# as14120_x31_usb.net
KiCad netlist of a schematic drawn in Altium Designer
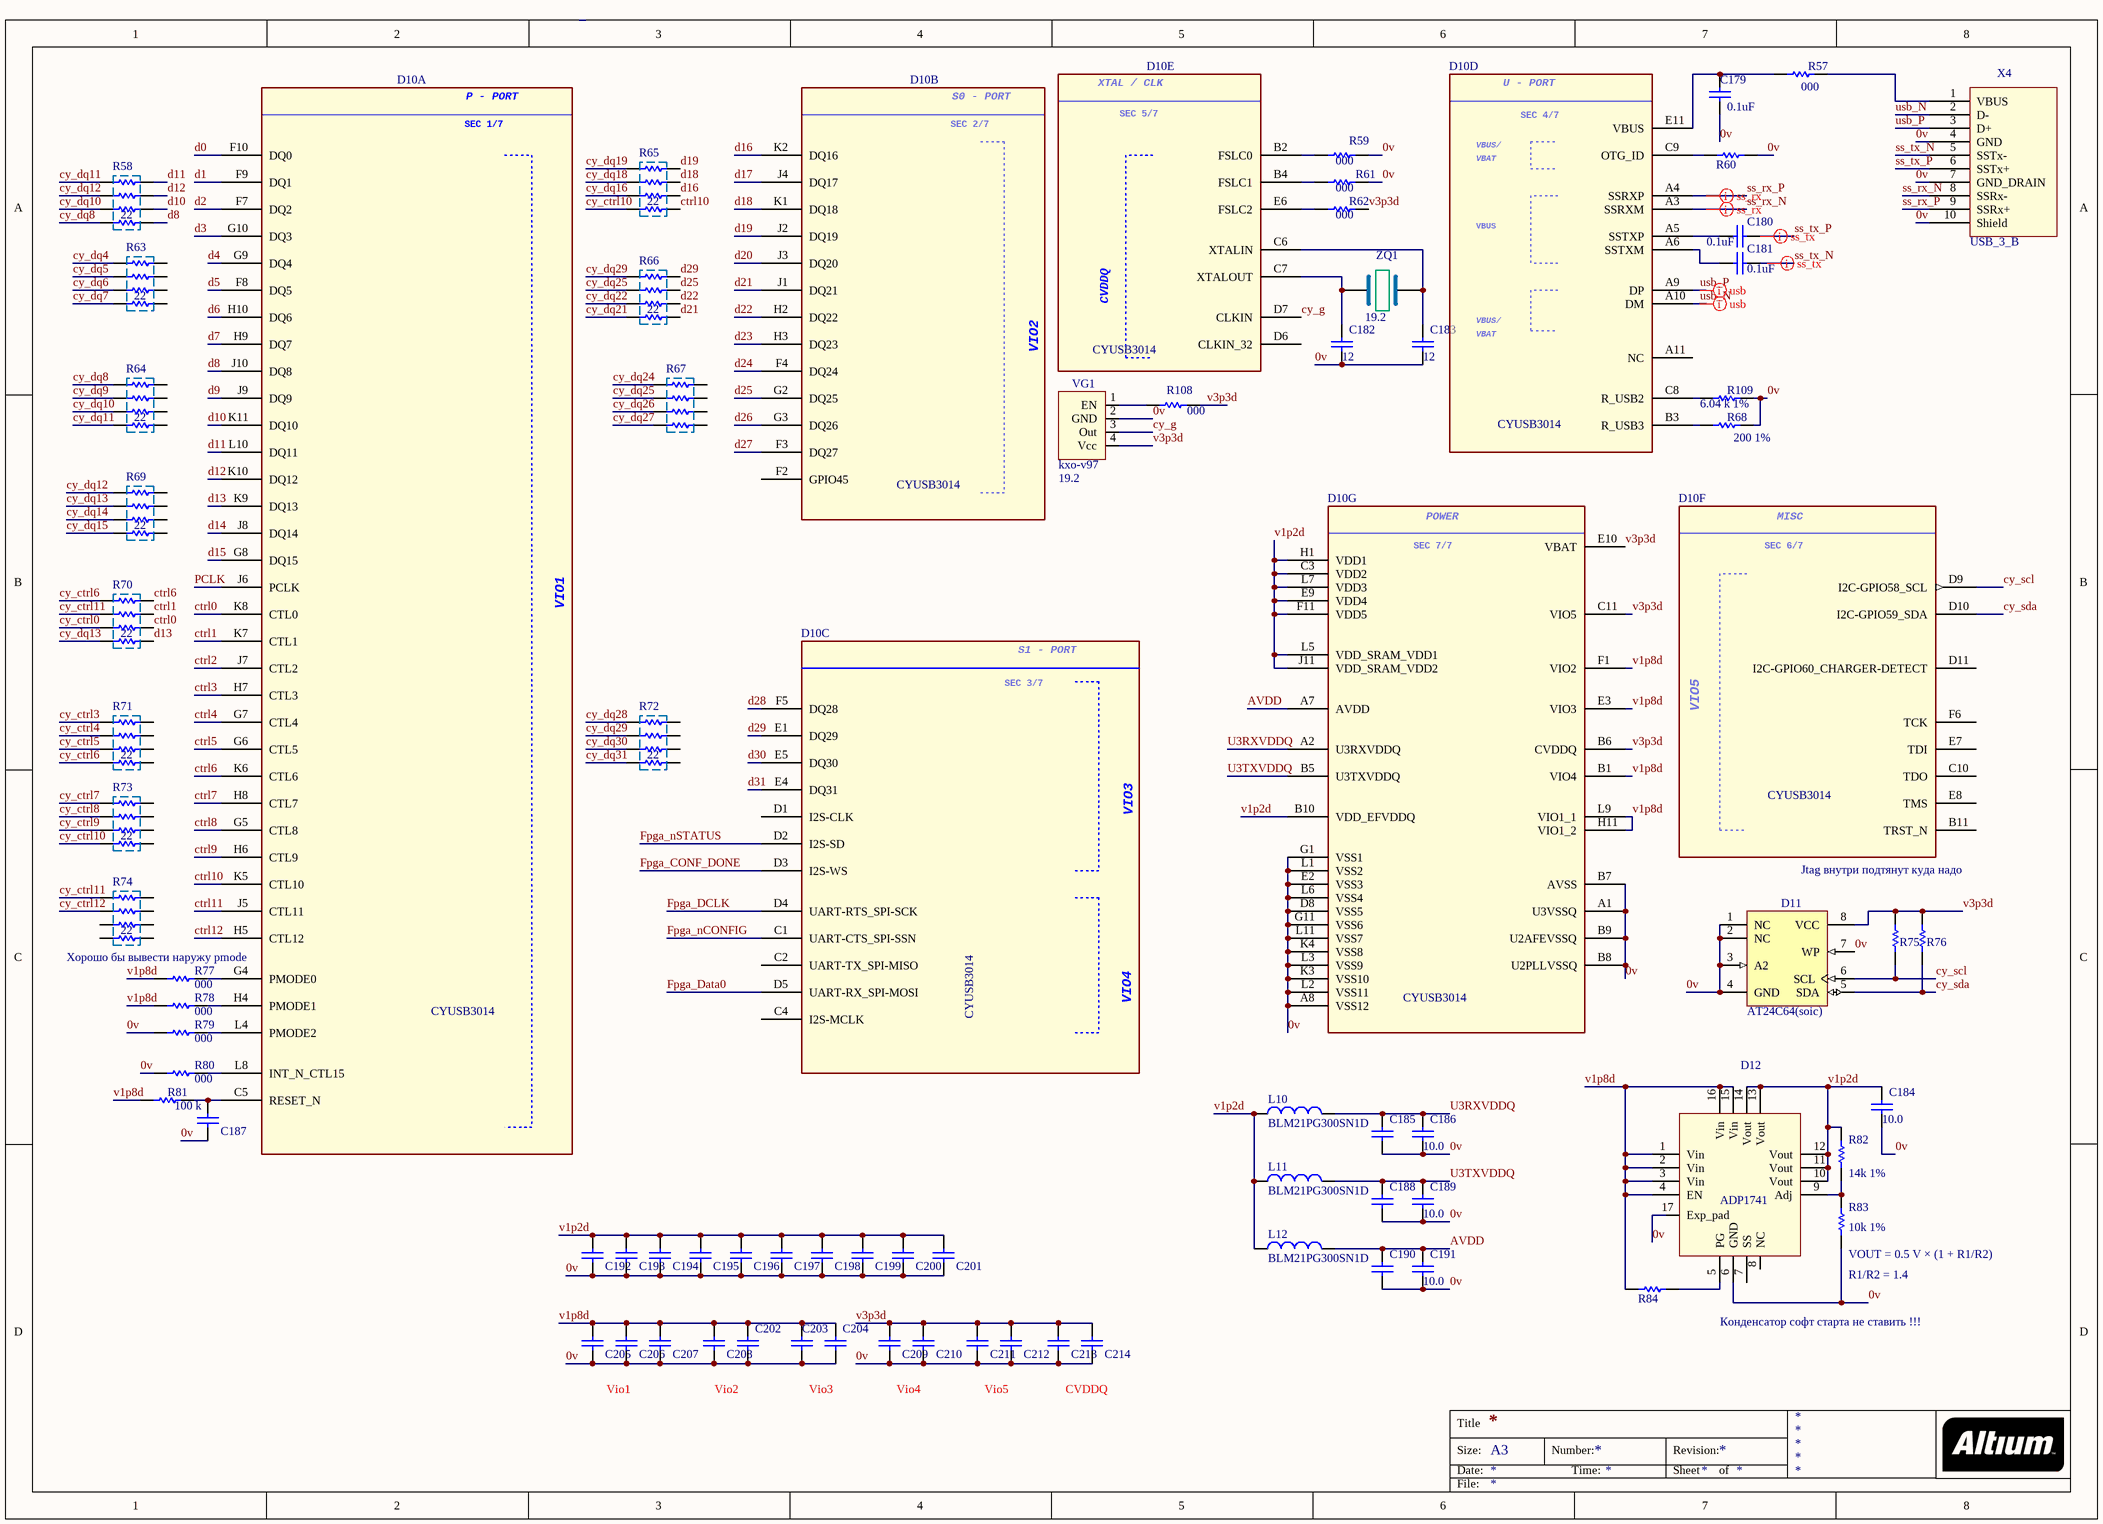
[diagram p0: as14120_x31_usb.SchDoc]

(export (version "E")
  (design (tool "Eeschema 10.0.6"))
  (components
    (comp (ref "C179")
      (value "0.1uF")
      (footprint "CAPC0402(1005)60_M")
      (description "CAP 1uF 10V ±20% 0402 (1005 Metric) Thickness 0.6mm SMD")
      (fields (field (name "TOLERANCE") "±20%") (field (name "Comment") "CAP 1uF 10V 0402(1005)"))
      (libsource (lib "as14120") (part "CAP_0402"))
    )
    (comp (ref "C180")
      (value "0.1uF")
      (footprint "CAPC0402(1005)60_M")
      (description "CAP 1uF 10V ±20% 0402 (1005 Metric) Thickness 0.6mm SMD")
      (fields (field (name "TOLERANCE") "±20%") (field (name "Comment") "CAP 1uF 10V 0402(1005)"))
      (libsource (lib "as14120") (part "CAP_0402"))
    )
    (comp (ref "C181")
      (value "0.1uF")
      (footprint "CAPC0402(1005)60_M")
      (description "CAP 1uF 10V ±20% 0402 (1005 Metric) Thickness 0.6mm SMD")
      (fields (field (name "TOLERANCE") "±20%") (field (name "Comment") "CAP 1uF 10V 0402(1005)"))
      (libsource (lib "as14120") (part "CAP_0402"))
    )
    (comp (ref "C182")
      (value "12")
      (footprint "CAPC0805(2012)100_N")
      (fields (field (name "Comment") "CAP_0805"))
      (libsource (lib "as14120") (part "CAP_0805"))
    )
    (comp (ref "C183")
      (value "12")
      (footprint "CAPC0805(2012)100_N")
      (fields (field (name "Comment") "CAP_0805"))
      (libsource (lib "as14120") (part "CAP_0805"))
    )
    (comp (ref "C184")
      (value "10.0")
      (footprint "CAPC0805(2012)100_N")
      (fields (field (name "Comment") "CAP_0805"))
      (libsource (lib "as14120") (part "CAP_0805"))
    )
    (comp (ref "C185")
      (value "CAP 1uF 10V 0402(1005)")
      (footprint "CAPC0402(1005)60_M")
      (description "CAP 1uF 10V ±20% 0402 (1005 Metric) Thickness 0.6mm SMD")
      (fields (field (name "TOLERANCE") "±20%"))
      (libsource (lib "as14120") (part "CAP_0402"))
    )
    (comp (ref "C186")
      (value "10.0")
      (footprint "CAPC0805(2012)100_N")
      (fields (field (name "Comment") "CAP_0805"))
      (libsource (lib "as14120") (part "CAP_0805"))
    )
    (comp (ref "C187")
      (value "CAP 1uF 10V 0402(1005)")
      (footprint "CAPC0402(1005)60_M")
      (description "CAP 1uF 10V ±20% 0402 (1005 Metric) Thickness 0.6mm SMD")
      (fields (field (name "TOLERANCE") "±20%"))
      (libsource (lib "as14120") (part "CAP_0402"))
    )
    (comp (ref "C188")
      (value "CAP 1uF 10V 0402(1005)")
      (footprint "CAPC0402(1005)60_M")
      (description "CAP 1uF 10V ±20% 0402 (1005 Metric) Thickness 0.6mm SMD")
      (fields (field (name "TOLERANCE") "±20%"))
      (libsource (lib "as14120") (part "CAP_0402"))
    )
    (comp (ref "C189")
      (value "10.0")
      (footprint "CAPC0805(2012)100_N")
      (fields (field (name "Comment") "CAP_0805"))
      (libsource (lib "as14120") (part "CAP_0805"))
    )
    (comp (ref "C190")
      (value "CAP 1uF 10V 0402(1005)")
      (footprint "CAPC0402(1005)60_M")
      (description "CAP 1uF 10V ±20% 0402 (1005 Metric) Thickness 0.6mm SMD")
      (fields (field (name "TOLERANCE") "±20%"))
      (libsource (lib "as14120") (part "CAP_0402"))
    )
    (comp (ref "C191")
      (value "10.0")
      (footprint "CAPC0805(2012)100_N")
      (fields (field (name "Comment") "CAP_0805"))
      (libsource (lib "as14120") (part "CAP_0805"))
    )
    (comp (ref "C192")
      (value "CAP 1uF 10V 0402(1005)")
      (footprint "CAPC0402(1005)60_M")
      (description "CAP 1uF 10V ±20% 0402 (1005 Metric) Thickness 0.6mm SMD")
      (fields (field (name "TOLERANCE") "±20%"))
      (libsource (lib "as14120") (part "CAP_0402"))
    )
    (comp (ref "C193")
      (value "CAP 1uF 10V 0402(1005)")
      (footprint "CAPC0402(1005)60_M")
      (description "CAP 1uF 10V ±20% 0402 (1005 Metric) Thickness 0.6mm SMD")
      (fields (field (name "TOLERANCE") "±20%"))
      (libsource (lib "as14120") (part "CAP_0402"))
    )
    (comp (ref "C194")
      (value "CAP 1uF 10V 0402(1005)")
      (footprint "CAPC0402(1005)60_M")
      (description "CAP 1uF 10V ±20% 0402 (1005 Metric) Thickness 0.6mm SMD")
      (fields (field (name "TOLERANCE") "±20%"))
      (libsource (lib "as14120") (part "CAP_0402"))
    )
    (comp (ref "C195")
      (value "CAP 1uF 10V 0402(1005)")
      (footprint "CAPC0402(1005)60_M")
      (description "CAP 1uF 10V ±20% 0402 (1005 Metric) Thickness 0.6mm SMD")
      (fields (field (name "TOLERANCE") "±20%"))
      (libsource (lib "as14120") (part "CAP_0402"))
    )
    (comp (ref "C196")
      (value "CAP 1uF 10V 0402(1005)")
      (footprint "CAPC0402(1005)60_M")
      (description "CAP 1uF 10V ±20% 0402 (1005 Metric) Thickness 0.6mm SMD")
      (fields (field (name "TOLERANCE") "±20%"))
      (libsource (lib "as14120") (part "CAP_0402"))
    )
    (comp (ref "C197")
      (value "CAP 1uF 10V 0402(1005)")
      (footprint "CAPC0402(1005)60_M")
      (description "CAP 1uF 10V ±20% 0402 (1005 Metric) Thickness 0.6mm SMD")
      (fields (field (name "TOLERANCE") "±20%"))
      (libsource (lib "as14120") (part "CAP_0402"))
    )
    (comp (ref "C198")
      (value "CAP 1uF 10V 0402(1005)")
      (footprint "CAPC0402(1005)60_M")
      (description "CAP 1uF 10V ±20% 0402 (1005 Metric) Thickness 0.6mm SMD")
      (fields (field (name "TOLERANCE") "±20%"))
      (libsource (lib "as14120") (part "CAP_0402"))
    )
    (comp (ref "C199")
      (value "CAP 1uF 10V 0402(1005)")
      (footprint "CAPC0402(1005)60_M")
      (description "CAP 1uF 10V ±20% 0402 (1005 Metric) Thickness 0.6mm SMD")
      (fields (field (name "TOLERANCE") "±20%"))
      (libsource (lib "as14120") (part "CAP_0402"))
    )
    (comp (ref "C200")
      (value "CAP 1uF 10V 0402(1005)")
      (footprint "CAPC0402(1005)60_M")
      (description "CAP 1uF 10V ±20% 0402 (1005 Metric) Thickness 0.6mm SMD")
      (fields (field (name "TOLERANCE") "±20%"))
      (libsource (lib "as14120") (part "CAP_0402"))
    )
    (comp (ref "C201")
      (value "CAP 1uF 10V 0402(1005)")
      (footprint "CAPC0402(1005)60_M")
      (description "CAP 1uF 10V ±20% 0402 (1005 Metric) Thickness 0.6mm SMD")
      (fields (field (name "TOLERANCE") "±20%"))
      (libsource (lib "as14120") (part "CAP_0402"))
    )
    (comp (ref "C202")
      (value "CAP 1uF 10V 0402(1005)")
      (footprint "CAPC0402(1005)60_M")
      (description "CAP 1uF 10V ±20% 0402 (1005 Metric) Thickness 0.6mm SMD")
      (fields (field (name "TOLERANCE") "±20%"))
      (libsource (lib "as14120") (part "CAP_0402"))
    )
    (comp (ref "C203")
      (value "CAP 1uF 10V 0402(1005)")
      (footprint "CAPC0402(1005)60_M")
      (description "CAP 1uF 10V ±20% 0402 (1005 Metric) Thickness 0.6mm SMD")
      (fields (field (name "TOLERANCE") "±20%"))
      (libsource (lib "as14120") (part "CAP_0402"))
    )
    (comp (ref "C204")
      (value "CAP 1uF 10V 0402(1005)")
      (footprint "CAPC0402(1005)60_M")
      (description "CAP 1uF 10V ±20% 0402 (1005 Metric) Thickness 0.6mm SMD")
      (fields (field (name "TOLERANCE") "±20%"))
      (libsource (lib "as14120") (part "CAP_0402"))
    )
    (comp (ref "C205")
      (value "CAP 1uF 10V 0402(1005)")
      (footprint "CAPC0402(1005)60_M")
      (description "CAP 1uF 10V ±20% 0402 (1005 Metric) Thickness 0.6mm SMD")
      (fields (field (name "TOLERANCE") "±20%"))
      (libsource (lib "as14120") (part "CAP_0402"))
    )
    (comp (ref "C206")
      (value "CAP 1uF 10V 0402(1005)")
      (footprint "CAPC0402(1005)60_M")
      (description "CAP 1uF 10V ±20% 0402 (1005 Metric) Thickness 0.6mm SMD")
      (fields (field (name "TOLERANCE") "±20%"))
      (libsource (lib "as14120") (part "CAP_0402"))
    )
    (comp (ref "C207")
      (value "CAP 1uF 10V 0402(1005)")
      (footprint "CAPC0402(1005)60_M")
      (description "CAP 1uF 10V ±20% 0402 (1005 Metric) Thickness 0.6mm SMD")
      (fields (field (name "TOLERANCE") "±20%"))
      (libsource (lib "as14120") (part "CAP_0402"))
    )
    (comp (ref "C208")
      (value "CAP 1uF 10V 0402(1005)")
      (footprint "CAPC0402(1005)60_M")
      (description "CAP 1uF 10V ±20% 0402 (1005 Metric) Thickness 0.6mm SMD")
      (fields (field (name "TOLERANCE") "±20%"))
      (libsource (lib "as14120") (part "CAP_0402"))
    )
    (comp (ref "C209")
      (value "CAP 1uF 10V 0402(1005)")
      (footprint "CAPC0402(1005)60_M")
      (description "CAP 1uF 10V ±20% 0402 (1005 Metric) Thickness 0.6mm SMD")
      (fields (field (name "TOLERANCE") "±20%"))
      (libsource (lib "as14120") (part "CAP_0402"))
    )
    (comp (ref "C210")
      (value "CAP 1uF 10V 0402(1005)")
      (footprint "CAPC0402(1005)60_M")
      (description "CAP 1uF 10V ±20% 0402 (1005 Metric) Thickness 0.6mm SMD")
      (fields (field (name "TOLERANCE") "±20%"))
      (libsource (lib "as14120") (part "CAP_0402"))
    )
    (comp (ref "C211")
      (value "CAP 1uF 10V 0402(1005)")
      (footprint "CAPC0402(1005)60_M")
      (description "CAP 1uF 10V ±20% 0402 (1005 Metric) Thickness 0.6mm SMD")
      (fields (field (name "TOLERANCE") "±20%"))
      (libsource (lib "as14120") (part "CAP_0402"))
    )
    (comp (ref "C212")
      (value "CAP 1uF 10V 0402(1005)")
      (footprint "CAPC0402(1005)60_M")
      (description "CAP 1uF 10V ±20% 0402 (1005 Metric) Thickness 0.6mm SMD")
      (fields (field (name "TOLERANCE") "±20%"))
      (libsource (lib "as14120") (part "CAP_0402"))
    )
    (comp (ref "C213")
      (value "CAP 1uF 10V 0402(1005)")
      (footprint "CAPC0402(1005)60_M")
      (description "CAP 1uF 10V ±20% 0402 (1005 Metric) Thickness 0.6mm SMD")
      (fields (field (name "TOLERANCE") "±20%"))
      (libsource (lib "as14120") (part "CAP_0402"))
    )
    (comp (ref "C214")
      (value "CAP 1uF 10V 0402(1005)")
      (footprint "CAPC0402(1005)60_M")
      (description "CAP 1uF 10V ±20% 0402 (1005 Metric) Thickness 0.6mm SMD")
      (fields (field (name "TOLERANCE") "±20%"))
      (libsource (lib "as14120") (part "CAP_0402"))
    )
    (comp (ref "D10")
      (value "CYUSB3014")
      (footprint "BGA121C80P11X11")
      (libsource (lib "as14120") (part "CYUSB3014-BZXC"))
    )
    (comp (ref "D11")
      (value "AT24C64(soic)")
      (footprint "8S1_N")
      (libsource (lib "Atmel Serial EEPROM") (part "AT24C08BN-SP25-T"))
    )
    (comp (ref "D12") (value "ADP1741") (footprint "CP-16-4_N") (libsource (lib "as14120") (part "ADP1741")))
    (comp (ref "L10")
      (value "BLM21PG300SN1D")
      (footprint "CAPC0805(2012)100_N")
      (libsource (lib "as14120") (part "Ferrite_beat"))
    )
    (comp (ref "L11")
      (value "BLM21PG300SN1D")
      (footprint "CAPC0805(2012)100_N")
      (libsource (lib "as14120") (part "Ferrite_beat"))
    )
    (comp (ref "L12")
      (value "BLM21PG300SN1D")
      (footprint "CAPC0805(2012)100_N")
      (libsource (lib "as14120") (part "Ferrite_beat"))
    )
    (comp (ref "R57")
      (value "000")
      (footprint "RESC0805(2012)_L")
      (description "1K 0.125W 1% 0805 (2012 Metric)  SMD")
      (fields (field (name "TOLERANCE") "1 %") (field (name "POWER") "0.125 W"))
      (libsource (lib "as14120") (part "RES_0805"))
    )
    (comp (ref "R58") (value "22") (footprint "CAY16") (libsource (lib "as14120") (part "cay16-J4")))
    (comp (ref "R59")
      (value "000")
      (footprint "RESC0603(1608)_L")
      (description "1K 0.1W 5% 0603 (1608 Metric)  SMD")
      (fields (field (name "TOLERANCE") "5 %") (field (name "POWER") "0.1 W"))
      (libsource (lib "as14120") (part "RES_0603"))
    )
    (comp (ref "R60")
      (value "???")
      (footprint "RESC0603(1608)_L")
      (description "1K 0.1W 5% 0603 (1608 Metric)  SMD")
      (fields (field (name "TOLERANCE") "5 %") (field (name "POWER") "0.1 W"))
      (libsource (lib "as14120") (part "RES_0603"))
    )
    (comp (ref "R61")
      (value "000")
      (footprint "RESC0603(1608)_L")
      (description "1K 0.1W 5% 0603 (1608 Metric)  SMD")
      (fields (field (name "TOLERANCE") "5 %") (field (name "POWER") "0.1 W"))
      (libsource (lib "as14120") (part "RES_0603"))
    )
    (comp (ref "R62")
      (value "000")
      (footprint "RESC0603(1608)_L")
      (description "1K 0.1W 5% 0603 (1608 Metric)  SMD")
      (fields (field (name "TOLERANCE") "5 %") (field (name "POWER") "0.1 W"))
      (libsource (lib "as14120") (part "RES_0603"))
    )
    (comp (ref "R63") (value "22") (footprint "CAY16") (libsource (lib "as14120") (part "cay16-J4")))
    (comp (ref "R64") (value "22") (footprint "CAY16") (libsource (lib "as14120") (part "cay16-J4")))
    (comp (ref "R65") (value "22") (footprint "CAY16") (libsource (lib "as14120") (part "cay16-J4")))
    (comp (ref "R66") (value "22") (footprint "CAY16") (libsource (lib "as14120") (part "cay16-J4")))
    (comp (ref "R67") (value "~") (footprint "CAY16") (libsource (lib "as14120") (part "cay16-J4")))
    (comp (ref "R68")
      (value "200 1%")
      (footprint "RESC0805(2012)_L")
      (description "1K 0.125W 1% 0805 (2012 Metric)  SMD")
      (fields (field (name "TOLERANCE") "1 %") (field (name "POWER") "0.125 W"))
      (libsource (lib "as14120") (part "RES_0805"))
    )
    (comp (ref "R69") (value "22") (footprint "CAY16") (libsource (lib "as14120") (part "cay16-J4")))
    (comp (ref "R70") (value "22") (footprint "CAY16") (libsource (lib "as14120") (part "cay16-J4")))
    (comp (ref "R71") (value "22") (footprint "CAY16") (libsource (lib "as14120") (part "cay16-J4")))
    (comp (ref "R72") (value "22") (footprint "CAY16") (libsource (lib "as14120") (part "cay16-J4")))
    (comp (ref "R73") (value "22") (footprint "CAY16") (libsource (lib "as14120") (part "cay16-J4")))
    (comp (ref "R74") (value "22") (footprint "CAY16") (libsource (lib "as14120") (part "cay16-J4")))
    (comp (ref "R75")
      (value "1K 5% 0603(1608)")
      (footprint "RESC0603(1608)_L")
      (description "1K 0.1W 5% 0603 (1608 Metric)  SMD")
      (fields (field (name "TOLERANCE") "5 %") (field (name "POWER") "0.1 W"))
      (libsource (lib "as14120") (part "RES_0603"))
    )
    (comp (ref "R76")
      (value "1K 5% 0603(1608)")
      (footprint "RESC0603(1608)_L")
      (description "1K 0.1W 5% 0603 (1608 Metric)  SMD")
      (fields (field (name "TOLERANCE") "5 %") (field (name "POWER") "0.1 W"))
      (libsource (lib "as14120") (part "RES_0603"))
    )
    (comp (ref "R77")
      (value "000")
      (footprint "RESC0603(1608)_L")
      (description "1K 0.1W 5% 0603 (1608 Metric)  SMD")
      (fields (field (name "TOLERANCE") "5 %") (field (name "POWER") "0.1 W"))
      (libsource (lib "as14120") (part "RES_0603"))
    )
    (comp (ref "R78")
      (value "000")
      (footprint "RESC0603(1608)_L")
      (description "1K 0.1W 5% 0603 (1608 Metric)  SMD")
      (fields (field (name "TOLERANCE") "5 %") (field (name "POWER") "0.1 W"))
      (libsource (lib "as14120") (part "RES_0603"))
    )
    (comp (ref "R79")
      (value "000")
      (footprint "RESC0603(1608)_L")
      (description "1K 0.1W 5% 0603 (1608 Metric)  SMD")
      (fields (field (name "TOLERANCE") "5 %") (field (name "POWER") "0.1 W"))
      (libsource (lib "as14120") (part "RES_0603"))
    )
    (comp (ref "R80")
      (value "000")
      (footprint "RESC0603(1608)_L")
      (description "1K 0.1W 5% 0603 (1608 Metric)  SMD")
      (fields (field (name "TOLERANCE") "5 %") (field (name "POWER") "0.1 W"))
      (libsource (lib "as14120") (part "RES_0603"))
    )
    (comp (ref "R81")
      (value "100 k")
      (footprint "RESC0603(1608)_L")
      (description "1K 0.1W 5% 0603 (1608 Metric)  SMD")
      (fields (field (name "TOLERANCE") "5 %") (field (name "POWER") "0.1 W"))
      (libsource (lib "as14120") (part "RES_0603"))
    )
    (comp (ref "R82")
      (value "14k 1%")
      (footprint "RESC0805(2012)_L")
      (description "1K 0.125W 1% 0805 (2012 Metric)  SMD")
      (fields (field (name "TOLERANCE") "1 %") (field (name "POWER") "0.125 W"))
      (libsource (lib "as14120") (part "RES_0805"))
    )
    (comp (ref "R83")
      (value "10k 1%")
      (footprint "RESC0805(2012)_L")
      (description "1K 0.125W 1% 0805 (2012 Metric)  SMD")
      (fields (field (name "TOLERANCE") "1 %") (field (name "POWER") "0.125 W"))
      (libsource (lib "as14120") (part "RES_0805"))
    )
    (comp (ref "R84")
      (value "1K 5% 0603(1608)")
      (footprint "RESC0603(1608)_L")
      (description "1K 0.1W 5% 0603 (1608 Metric)  SMD")
      (fields (field (name "TOLERANCE") "5 %") (field (name "POWER") "0.1 W"))
      (libsource (lib "as14120") (part "RES_0603"))
    )
    (comp (ref "R108")
      (value "000")
      (footprint "RESC0603(1608)_L")
      (description "1K 0.1W 5% 0603 (1608 Metric)  SMD")
      (fields (field (name "TOLERANCE") "5 %") (field (name "POWER") "0.1 W"))
      (libsource (lib "as14120") (part "RES_0603"))
    )
    (comp (ref "R109")
      (value "6.04 k 1%")
      (footprint "RESC0805(2012)_L")
      (description "1K 0.125W 1% 0805 (2012 Metric)  SMD")
      (fields (field (name "TOLERANCE") "1 %") (field (name "POWER") "0.125 W"))
      (libsource (lib "as14120") (part "RES_0805"))
    )
    (comp (ref "VG1")
      (value "kxo-v97")
      (footprint "kxo-v97")
      (fields (field (name "ALTIUM_VALUE") "19.2"))
      (libsource (lib "as14120") (part "kxo-v97"))
    )
    (comp (ref "X4") (value "USB_3_B") (footprint "USB3_B") (libsource (lib "as14120") (part "USB_3_B")))
    (comp (ref "ZQ1")
      (value "19.2")
      (footprint "BCY-W2/E4.7")
      (fields (field (name "Comment") "Resonator"))
      (libsource (lib "as14120") (part "Resonator"))
    )
  )
  (nets
    (net (code "1") (name "/0v") (class "Default")
      (node (ref "C179") (pin "2") (pinfunction "2_2") (pintype "passive"))
      (node (ref "C182") (pin "1") (pinfunction "1_1") (pintype "passive"))
      (node (ref "C183") (pin "1") (pinfunction "1_1") (pintype "passive"))
      (node (ref "C184") (pin "1") (pinfunction "1_1") (pintype "passive"))
      (node (ref "C185") (pin "1") (pinfunction "1_1") (pintype "passive"))
      (node (ref "C186") (pin "1") (pinfunction "1_1") (pintype "passive"))
      (node (ref "C187") (pin "1") (pinfunction "1_1") (pintype "passive"))
      (node (ref "C188") (pin "1") (pinfunction "1_1") (pintype "passive"))
      (node (ref "C189") (pin "1") (pinfunction "1_1") (pintype "passive"))
      (node (ref "C190") (pin "1") (pinfunction "1_1") (pintype "passive"))
      (node (ref "C191") (pin "1") (pinfunction "1_1") (pintype "passive"))
      (node (ref "C192") (pin "1") (pinfunction "1_1") (pintype "passive"))
      (node (ref "C193") (pin "1") (pinfunction "1_1") (pintype "passive"))
      (node (ref "C194") (pin "1") (pinfunction "1_1") (pintype "passive"))
      (node (ref "C195") (pin "1") (pinfunction "1_1") (pintype "passive"))
      (node (ref "C196") (pin "1") (pinfunction "1_1") (pintype "passive"))
      (node (ref "C197") (pin "1") (pinfunction "1_1") (pintype "passive"))
      (node (ref "C198") (pin "1") (pinfunction "1_1") (pintype "passive"))
      (node (ref "C199") (pin "1") (pinfunction "1_1") (pintype "passive"))
      (node (ref "C200") (pin "1") (pinfunction "1_1") (pintype "passive"))
      (node (ref "C201") (pin "1") (pinfunction "1_1") (pintype "passive"))
      (node (ref "C202") (pin "1") (pinfunction "1_1") (pintype "passive"))
      (node (ref "C203") (pin "1") (pinfunction "1_1") (pintype "passive"))
      (node (ref "C204") (pin "1") (pinfunction "1_1") (pintype "passive"))
      (node (ref "C205") (pin "1") (pinfunction "1_1") (pintype "passive"))
      (node (ref "C206") (pin "1") (pinfunction "1_1") (pintype "passive"))
      (node (ref "C207") (pin "1") (pinfunction "1_1") (pintype "passive"))
      (node (ref "C208") (pin "1") (pinfunction "1_1") (pintype "passive"))
      (node (ref "C209") (pin "1") (pinfunction "1_1") (pintype "passive"))
      (node (ref "C210") (pin "1") (pinfunction "1_1") (pintype "passive"))
      (node (ref "C211") (pin "1") (pinfunction "1_1") (pintype "passive"))
      (node (ref "C212") (pin "1") (pinfunction "1_1") (pintype "passive"))
      (node (ref "C213") (pin "1") (pinfunction "1_1") (pintype "passive"))
      (node (ref "C214") (pin "1") (pinfunction "1_1") (pintype "passive"))
      (node (ref "D10") (pin "A1") (pinfunction "U3VSSQ_A1") (pintype "passive"))
      (node (ref "D10") (pin "A8") (pinfunction "VSS12_A8") (pintype "passive"))
      (node (ref "D10") (pin "B7") (pinfunction "AVSS_B7") (pintype "passive"))
      (node (ref "D10") (pin "B8") (pinfunction "U2PLLVSSQ_B8") (pintype "passive"))
      (node (ref "D10") (pin "B9") (pinfunction "U2AFEVSSQ_B9") (pintype "passive"))
      (node (ref "D10") (pin "D8") (pinfunction "VSS5_D8") (pintype "passive"))
      (node (ref "D10") (pin "E2") (pinfunction "VSS3_E2") (pintype "passive"))
      (node (ref "D10") (pin "G1") (pinfunction "VSS1_G1") (pintype "passive"))
      (node (ref "D10") (pin "G11") (pinfunction "VSS6_G11") (pintype "passive"))
      (node (ref "D10") (pin "K3") (pinfunction "VSS10_K3") (pintype "passive"))
      (node (ref "D10") (pin "K4") (pinfunction "VSS8_K4") (pintype "passive"))
      (node (ref "D10") (pin "L1") (pinfunction "VSS2_L1") (pintype "passive"))
      (node (ref "D10") (pin "L11") (pinfunction "VSS7_L11") (pintype "passive"))
      (node (ref "D10") (pin "L2") (pinfunction "VSS11_L2") (pintype "passive"))
      (node (ref "D10") (pin "L3") (pinfunction "VSS9_L3") (pintype "passive"))
      (node (ref "D10") (pin "L6") (pinfunction "VSS4_L6") (pintype "passive"))
      (node (ref "D11") (pin "1") (pinfunction "NC_1") (pintype "passive"))
      (node (ref "D11") (pin "2") (pinfunction "NC_2") (pintype "passive"))
      (node (ref "D11") (pin "3") (pinfunction "A2_3") (pintype "input"))
      (node (ref "D11") (pin "4") (pinfunction "GND_4") (pintype "power_in"))
      (node (ref "D11") (pin "7") (pinfunction "WP_7") (pintype "input"))
      (node (ref "D12") (pin "17") (pinfunction "Exp_pad_17") (pintype "passive"))
      (node (ref "D12") (pin "6") (pinfunction "GND_6") (pintype "passive"))
      (node (ref "R109") (pin "2") (pinfunction "2_2") (pintype "passive"))
      (node (ref "R59") (pin "1") (pinfunction "1_1") (pintype "passive"))
      (node (ref "R60") (pin "2") (pinfunction "2_2") (pintype "passive"))
      (node (ref "R61") (pin "1") (pinfunction "1_1") (pintype "passive"))
      (node (ref "R68") (pin "2") (pinfunction "2_2") (pintype "passive"))
      (node (ref "R79") (pin "2") (pinfunction "2_2") (pintype "passive"))
      (node (ref "R80") (pin "2") (pinfunction "2_2") (pintype "passive"))
      (node (ref "R83") (pin "1") (pinfunction "1_1") (pintype "passive"))
      (node (ref "VG1") (pin "2") (pinfunction "GND_2") (pintype "passive"))
      (node (ref "X4") (pin "10") (pinfunction "Shield_10") (pintype "passive"))
      (node (ref "X4") (pin "4") (pinfunction "GND_4") (pintype "passive"))
      (node (ref "X4") (pin "7") (pinfunction "GND_DRAIN_7") (pintype "passive"))
    )
    (net (code "2") (name "/AVDD") (class "Default")
      (node (ref "C190") (pin "2") (pinfunction "2_2") (pintype "passive"))
      (node (ref "C191") (pin "2") (pinfunction "2_2") (pintype "passive"))
      (node (ref "D10") (pin "A7") (pinfunction "AVDD_A7") (pintype "passive"))
      (node (ref "L12") (pin "2") (pinfunction "2_2") (pintype "passive"))
    )
    (net (code "3") (name "/Fpga_CONF_DONE") (class "Default")
      (node (ref "D10") (pin "D3") (pinfunction "I2S-WS_D3") (pintype "passive"))
    )
    (net (code "4") (name "/Fpga_DCLK") (class "Default")
      (node (ref "D10") (pin "D4") (pinfunction "UART-RTS_SPI-SCK_D4") (pintype "passive"))
    )
    (net (code "5") (name "/Fpga_Data0") (class "Default")
      (node (ref "D10") (pin "D5") (pinfunction "UART-RX_SPI-MOSI_D5") (pintype "passive"))
    )
    (net (code "6") (name "/Fpga_nCONFIG") (class "Default")
      (node (ref "D10") (pin "C1") (pinfunction "UART-CTS_SPI-SSN_C1") (pintype "passive"))
    )
    (net (code "7") (name "/Fpga_nSTATUS") (class "Default")
      (node (ref "D10") (pin "D2") (pinfunction "I2S-SD_D2") (pintype "passive"))
    )
    (net (code "8") (name "/PCLK") (class "Default")
      (node (ref "D10") (pin "J6") (pinfunction "PCLK_J6") (pintype "passive"))
    )
    (net (code "9") (name "/U3RXVDDQ") (class "Default")
      (node (ref "C185") (pin "2") (pinfunction "2_2") (pintype "passive"))
      (node (ref "C186") (pin "2") (pinfunction "2_2") (pintype "passive"))
      (node (ref "D10") (pin "A2") (pinfunction "U3RXVDDQ_A2") (pintype "passive"))
      (node (ref "L10") (pin "2") (pinfunction "2_2") (pintype "passive"))
    )
    (net (code "10") (name "/U3TXVDDQ") (class "Default")
      (node (ref "C188") (pin "2") (pinfunction "2_2") (pintype "passive"))
      (node (ref "C189") (pin "2") (pinfunction "2_2") (pintype "passive"))
      (node (ref "D10") (pin "B5") (pinfunction "U3TXVDDQ_B5") (pintype "passive"))
      (node (ref "L11") (pin "2") (pinfunction "2_2") (pintype "passive"))
    )
    (net (code "11") (name "/ctrl0") (class "Default")
      (node (ref "D10") (pin "K8") (pinfunction "CTL0_K8") (pintype "passive"))
      (node (ref "R70") (pin "6") (pinfunction "6_6") (pintype "passive"))
    )
    (net (code "12") (name "/ctrl1") (class "Default")
      (node (ref "D10") (pin "K7") (pinfunction "CTL1_K7") (pintype "passive"))
      (node (ref "R70") (pin "7") (pinfunction "7_7") (pintype "passive"))
    )
    (net (code "13") (name "/ctrl2") (class "Default")
      (node (ref "D10") (pin "J7") (pinfunction "CTL2_J7") (pintype "passive"))
    )
    (net (code "14") (name "/ctrl3") (class "Default")
      (node (ref "D10") (pin "H7") (pinfunction "CTL3_H7") (pintype "passive"))
    )
    (net (code "15") (name "/ctrl4") (class "Default")
      (node (ref "D10") (pin "G7") (pinfunction "CTL4_G7") (pintype "passive"))
    )
    (net (code "16") (name "/ctrl5") (class "Default")
      (node (ref "D10") (pin "G6") (pinfunction "CTL5_G6") (pintype "passive"))
    )
    (net (code "17") (name "/ctrl6") (class "Default")
      (node (ref "D10") (pin "K6") (pinfunction "CTL6_K6") (pintype "passive"))
      (node (ref "R70") (pin "8") (pinfunction "8_8") (pintype "passive"))
    )
    (net (code "18") (name "/ctrl7") (class "Default")
      (node (ref "D10") (pin "H8") (pinfunction "CTL7_H8") (pintype "passive"))
    )
    (net (code "19") (name "/ctrl8") (class "Default")
      (node (ref "D10") (pin "G5") (pinfunction "CTL8_G5") (pintype "passive"))
    )
    (net (code "20") (name "/ctrl9") (class "Default")
      (node (ref "D10") (pin "H6") (pinfunction "CTL9_H6") (pintype "passive"))
    )
    (net (code "21") (name "/ctrl10") (class "Default")
      (node (ref "D10") (pin "K5") (pinfunction "CTL10_K5") (pintype "passive"))
      (node (ref "R65") (pin "5") (pinfunction "5_5") (pintype "passive"))
    )
    (net (code "22") (name "/ctrl11") (class "Default")
      (node (ref "D10") (pin "J5") (pinfunction "CTL11_J5") (pintype "passive"))
    )
    (net (code "23") (name "/ctrl12") (class "Default")
      (node (ref "D10") (pin "H5") (pinfunction "CTL12_H5") (pintype "passive"))
    )
    (net (code "24") (name "/cy_ctrl0") (class "Default")
      (node (ref "R70") (pin "3") (pinfunction "3_3") (pintype "passive"))
    )
    (net (code "25") (name "/cy_ctrl3") (class "Default")
      (node (ref "R71") (pin "1") (pinfunction "1_1") (pintype "passive"))
    )
    (net (code "26") (name "/cy_ctrl4") (class "Default")
      (node (ref "R71") (pin "2") (pinfunction "2_2") (pintype "passive"))
    )
    (net (code "27") (name "/cy_ctrl5") (class "Default")
      (node (ref "R71") (pin "3") (pinfunction "3_3") (pintype "passive"))
    )
    (net (code "28") (name "/cy_ctrl6") (class "Default")
      (node (ref "R70") (pin "1") (pinfunction "1_1") (pintype "passive"))
      (node (ref "R71") (pin "4") (pinfunction "4_4") (pintype "passive"))
    )
    (net (code "29") (name "/cy_ctrl7") (class "Default")
      (node (ref "R73") (pin "1") (pinfunction "1_1") (pintype "passive"))
    )
    (net (code "30") (name "/cy_ctrl8") (class "Default")
      (node (ref "R73") (pin "2") (pinfunction "2_2") (pintype "passive"))
    )
    (net (code "31") (name "/cy_ctrl9") (class "Default")
      (node (ref "R73") (pin "3") (pinfunction "3_3") (pintype "passive"))
    )
    (net (code "32") (name "/cy_ctrl10") (class "Default")
      (node (ref "R65") (pin "4") (pinfunction "4_4") (pintype "passive"))
      (node (ref "R73") (pin "4") (pinfunction "4_4") (pintype "passive"))
    )
    (net (code "33") (name "/cy_ctrl11") (class "Default")
      (node (ref "R70") (pin "2") (pinfunction "2_2") (pintype "passive"))
      (node (ref "R74") (pin "1") (pinfunction "1_1") (pintype "passive"))
    )
    (net (code "34") (name "/cy_ctrl12") (class "Default")
      (node (ref "R74") (pin "2") (pinfunction "2_2") (pintype "passive"))
    )
    (net (code "35") (name "/cy_dq4") (class "Default")
      (node (ref "R63") (pin "1") (pinfunction "1_1") (pintype "passive"))
    )
    (net (code "36") (name "/cy_dq5") (class "Default")
      (node (ref "R63") (pin "2") (pinfunction "2_2") (pintype "passive"))
    )
    (net (code "37") (name "/cy_dq6") (class "Default")
      (node (ref "R63") (pin "3") (pinfunction "3_3") (pintype "passive"))
    )
    (net (code "38") (name "/cy_dq7") (class "Default")
      (node (ref "R63") (pin "4") (pinfunction "4_4") (pintype "passive"))
    )
    (net (code "39") (name "/cy_dq8") (class "Default")
      (node (ref "R58") (pin "4") (pinfunction "4_4") (pintype "passive"))
      (node (ref "R64") (pin "1") (pinfunction "1_1") (pintype "passive"))
    )
    (net (code "40") (name "/cy_dq9") (class "Default")
      (node (ref "R64") (pin "2") (pinfunction "2_2") (pintype "passive"))
    )
    (net (code "41") (name "/cy_dq10") (class "Default")
      (node (ref "R58") (pin "3") (pinfunction "3_3") (pintype "passive"))
      (node (ref "R64") (pin "3") (pinfunction "3_3") (pintype "passive"))
    )
    (net (code "42") (name "/cy_dq11") (class "Default")
      (node (ref "R58") (pin "1") (pinfunction "1_1") (pintype "passive"))
      (node (ref "R64") (pin "4") (pinfunction "4_4") (pintype "passive"))
    )
    (net (code "43") (name "/cy_dq12") (class "Default")
      (node (ref "R58") (pin "2") (pinfunction "2_2") (pintype "passive"))
      (node (ref "R69") (pin "1") (pinfunction "1_1") (pintype "passive"))
    )
    (net (code "44") (name "/cy_dq13") (class "Default")
      (node (ref "R69") (pin "2") (pinfunction "2_2") (pintype "passive"))
      (node (ref "R70") (pin "4") (pinfunction "4_4") (pintype "passive"))
    )
    (net (code "45") (name "/cy_dq14") (class "Default")
      (node (ref "R69") (pin "3") (pinfunction "3_3") (pintype "passive"))
    )
    (net (code "46") (name "/cy_dq15") (class "Default")
      (node (ref "R69") (pin "4") (pinfunction "4_4") (pintype "passive"))
    )
    (net (code "47") (name "/cy_dq16") (class "Default")
      (node (ref "R65") (pin "3") (pinfunction "3_3") (pintype "passive"))
    )
    (net (code "48") (name "/cy_dq18") (class "Default")
      (node (ref "R65") (pin "2") (pinfunction "2_2") (pintype "passive"))
    )
    (net (code "49") (name "/cy_dq19") (class "Default")
      (node (ref "R65") (pin "1") (pinfunction "1_1") (pintype "passive"))
    )
    (net (code "50") (name "/cy_dq21") (class "Default")
      (node (ref "R66") (pin "4") (pinfunction "4_4") (pintype "passive"))
    )
    (net (code "51") (name "/cy_dq22") (class "Default")
      (node (ref "R66") (pin "3") (pinfunction "3_3") (pintype "passive"))
    )
    (net (code "52") (name "/cy_dq24") (class "Default")
      (node (ref "R67") (pin "1") (pinfunction "1_1") (pintype "passive"))
    )
    (net (code "53") (name "/cy_dq25") (class "Default")
      (node (ref "R66") (pin "2") (pinfunction "2_2") (pintype "passive"))
      (node (ref "R67") (pin "2") (pinfunction "2_2") (pintype "passive"))
    )
    (net (code "54") (name "/cy_dq26") (class "Default")
      (node (ref "R67") (pin "3") (pinfunction "3_3") (pintype "passive"))
    )
    (net (code "55") (name "/cy_dq27") (class "Default")
      (node (ref "R67") (pin "4") (pinfunction "4_4") (pintype "passive"))
    )
    (net (code "56") (name "/cy_dq28") (class "Default")
      (node (ref "R72") (pin "1") (pinfunction "1_1") (pintype "passive"))
    )
    (net (code "57") (name "/cy_dq29") (class "Default")
      (node (ref "R66") (pin "1") (pinfunction "1_1") (pintype "passive"))
      (node (ref "R72") (pin "2") (pinfunction "2_2") (pintype "passive"))
    )
    (net (code "58") (name "/cy_dq30") (class "Default")
      (node (ref "R72") (pin "3") (pinfunction "3_3") (pintype "passive"))
    )
    (net (code "59") (name "/cy_dq31") (class "Default")
      (node (ref "R72") (pin "4") (pinfunction "4_4") (pintype "passive"))
    )
    (net (code "60") (name "/cy_g") (class "Default")
      (node (ref "D10") (pin "D7") (pinfunction "CLKIN_D7") (pintype "passive"))
      (node (ref "VG1") (pin "3") (pinfunction "Out_3") (pintype "passive"))
    )
    (net (code "61") (name "/cy_scl") (class "Default")
      (node (ref "D10") (pin "D9") (pinfunction "I2C-GPIO58_SCL_D9") (pintype "output"))
      (node (ref "D11") (pin "6") (pinfunction "SCL_6") (pintype "input"))
      (node (ref "R75") (pin "1") (pinfunction "1_1") (pintype "passive"))
    )
    (net (code "62") (name "/cy_sda") (class "Default")
      (node (ref "D10") (pin "D10") (pinfunction "I2C-GPIO59_SDA_D10") (pintype "passive"))
      (node (ref "D11") (pin "5") (pinfunction "SDA_5") (pintype "bidirectional"))
      (node (ref "R76") (pin "1") (pinfunction "1_1") (pintype "passive"))
    )
    (net (code "63") (name "/d0") (class "Default")
      (node (ref "D10") (pin "F10") (pinfunction "DQ0_F10") (pintype "passive"))
    )
    (net (code "64") (name "/d1") (class "Default")
      (node (ref "D10") (pin "F9") (pinfunction "DQ1_F9") (pintype "passive"))
    )
    (net (code "65") (name "/d2") (class "Default")
      (node (ref "D10") (pin "F7") (pinfunction "DQ2_F7") (pintype "passive"))
    )
    (net (code "66") (name "/d3") (class "Default")
      (node (ref "D10") (pin "G10") (pinfunction "DQ3_G10") (pintype "passive"))
    )
    (net (code "67") (name "/d4") (class "Default")
      (node (ref "D10") (pin "G9") (pinfunction "DQ4_G9") (pintype "passive"))
    )
    (net (code "68") (name "/d5") (class "Default")
      (node (ref "D10") (pin "F8") (pinfunction "DQ5_F8") (pintype "passive"))
    )
    (net (code "69") (name "/d6") (class "Default")
      (node (ref "D10") (pin "H10") (pinfunction "DQ6_H10") (pintype "passive"))
    )
    (net (code "70") (name "/d7") (class "Default")
      (node (ref "D10") (pin "H9") (pinfunction "DQ7_H9") (pintype "passive"))
    )
    (net (code "71") (name "/d8") (class "Default")
      (node (ref "D10") (pin "J10") (pinfunction "DQ8_J10") (pintype "passive"))
      (node (ref "R58") (pin "5") (pinfunction "5_5") (pintype "passive"))
    )
    (net (code "72") (name "/d9") (class "Default")
      (node (ref "D10") (pin "J9") (pinfunction "DQ9_J9") (pintype "passive"))
    )
    (net (code "73") (name "/d10") (class "Default")
      (node (ref "D10") (pin "K11") (pinfunction "DQ10_K11") (pintype "passive"))
      (node (ref "R58") (pin "6") (pinfunction "6_6") (pintype "passive"))
    )
    (net (code "74") (name "/d11") (class "Default")
      (node (ref "D10") (pin "L10") (pinfunction "DQ11_L10") (pintype "passive"))
      (node (ref "R58") (pin "8") (pinfunction "8_8") (pintype "passive"))
    )
    (net (code "75") (name "/d12") (class "Default")
      (node (ref "D10") (pin "K10") (pinfunction "DQ12_K10") (pintype "passive"))
      (node (ref "R58") (pin "7") (pinfunction "7_7") (pintype "passive"))
    )
    (net (code "76") (name "/d13") (class "Default")
      (node (ref "D10") (pin "K9") (pinfunction "DQ13_K9") (pintype "passive"))
      (node (ref "R70") (pin "5") (pinfunction "5_5") (pintype "passive"))
    )
    (net (code "77") (name "/d14") (class "Default")
      (node (ref "D10") (pin "J8") (pinfunction "DQ14_J8") (pintype "passive"))
    )
    (net (code "78") (name "/d15") (class "Default")
      (node (ref "D10") (pin "G8") (pinfunction "DQ15_G8") (pintype "passive"))
    )
    (net (code "79") (name "/d16") (class "Default")
      (node (ref "D10") (pin "K2") (pinfunction "DQ16_K2") (pintype "passive"))
      (node (ref "R65") (pin "6") (pinfunction "6_6") (pintype "passive"))
    )
    (net (code "80") (name "/d17") (class "Default")
      (node (ref "D10") (pin "J4") (pinfunction "DQ17_J4") (pintype "passive"))
    )
    (net (code "81") (name "/d18") (class "Default")
      (node (ref "D10") (pin "K1") (pinfunction "DQ18_K1") (pintype "passive"))
      (node (ref "R65") (pin "7") (pinfunction "7_7") (pintype "passive"))
    )
    (net (code "82") (name "/d19") (class "Default")
      (node (ref "D10") (pin "J2") (pinfunction "DQ19_J2") (pintype "passive"))
      (node (ref "R65") (pin "8") (pinfunction "8_8") (pintype "passive"))
    )
    (net (code "83") (name "/d20") (class "Default")
      (node (ref "D10") (pin "J3") (pinfunction "DQ20_J3") (pintype "passive"))
    )
    (net (code "84") (name "/d21") (class "Default")
      (node (ref "D10") (pin "J1") (pinfunction "DQ21_J1") (pintype "passive"))
      (node (ref "R66") (pin "5") (pinfunction "5_5") (pintype "passive"))
    )
    (net (code "85") (name "/d22") (class "Default")
      (node (ref "D10") (pin "H2") (pinfunction "DQ22_H2") (pintype "passive"))
      (node (ref "R66") (pin "6") (pinfunction "6_6") (pintype "passive"))
    )
    (net (code "86") (name "/d23") (class "Default")
      (node (ref "D10") (pin "H3") (pinfunction "DQ23_H3") (pintype "passive"))
    )
    (net (code "87") (name "/d24") (class "Default")
      (node (ref "D10") (pin "F4") (pinfunction "DQ24_F4") (pintype "passive"))
    )
    (net (code "88") (name "/d25") (class "Default")
      (node (ref "D10") (pin "G2") (pinfunction "DQ25_G2") (pintype "passive"))
      (node (ref "R66") (pin "7") (pinfunction "7_7") (pintype "passive"))
    )
    (net (code "89") (name "/d26") (class "Default")
      (node (ref "D10") (pin "G3") (pinfunction "DQ26_G3") (pintype "passive"))
    )
    (net (code "90") (name "/d27") (class "Default")
      (node (ref "D10") (pin "F3") (pinfunction "DQ27_F3") (pintype "passive"))
    )
    (net (code "91") (name "/d28") (class "Default")
      (node (ref "D10") (pin "F5") (pinfunction "DQ28_F5") (pintype "passive"))
    )
    (net (code "92") (name "/d29") (class "Default")
      (node (ref "D10") (pin "E1") (pinfunction "DQ29_E1") (pintype "passive"))
      (node (ref "R66") (pin "8") (pinfunction "8_8") (pintype "passive"))
    )
    (net (code "93") (name "/d30") (class "Default")
      (node (ref "D10") (pin "E5") (pinfunction "DQ30_E5") (pintype "passive"))
    )
    (net (code "94") (name "/d31") (class "Default")
      (node (ref "D10") (pin "E4") (pinfunction "DQ31_E4") (pintype "passive"))
    )
    (net (code "95") (name "/ss_rx_N") (class "Default")
      (node (ref "D10") (pin "A3") (pinfunction "SSRXM_A3") (pintype "passive"))
      (node (ref "X4") (pin "8") (pinfunction "SSRx-_8") (pintype "passive"))
    )
    (net (code "96") (name "/ss_rx_P") (class "Default")
      (node (ref "D10") (pin "A4") (pinfunction "SSRXP_A4") (pintype "passive"))
      (node (ref "X4") (pin "9") (pinfunction "SSRx+_9") (pintype "passive"))
    )
    (net (code "97") (name "/ss_tx_N") (class "Default")
      (node (ref "C181") (pin "1") (pinfunction "1_1") (pintype "passive"))
      (node (ref "X4") (pin "5") (pinfunction "SSTx-_5") (pintype "passive"))
    )
    (net (code "98") (name "/ss_tx_P") (class "Default")
      (node (ref "C180") (pin "1") (pinfunction "1_1") (pintype "passive"))
      (node (ref "X4") (pin "6") (pinfunction "SSTx+_6") (pintype "passive"))
    )
    (net (code "99") (name "/usb_N") (class "Default")
      (node (ref "D10") (pin "A10") (pinfunction "DM_A10") (pintype "passive"))
      (node (ref "X4") (pin "2") (pinfunction "D-_2") (pintype "passive"))
    )
    (net (code "100") (name "/usb_P") (class "Default")
      (node (ref "D10") (pin "A9") (pinfunction "DP_A9") (pintype "passive"))
      (node (ref "X4") (pin "3") (pinfunction "D+_3") (pintype "passive"))
    )
    (net (code "101") (name "/v1p2d") (class "Default")
      (node (ref "C184") (pin "2") (pinfunction "2_2") (pintype "passive"))
      (node (ref "C192") (pin "2") (pinfunction "2_2") (pintype "passive"))
      (node (ref "C193") (pin "2") (pinfunction "2_2") (pintype "passive"))
      (node (ref "C194") (pin "2") (pinfunction "2_2") (pintype "passive"))
      (node (ref "C195") (pin "2") (pinfunction "2_2") (pintype "passive"))
      (node (ref "C196") (pin "2") (pinfunction "2_2") (pintype "passive"))
      (node (ref "C197") (pin "2") (pinfunction "2_2") (pintype "passive"))
      (node (ref "C198") (pin "2") (pinfunction "2_2") (pintype "passive"))
      (node (ref "C199") (pin "2") (pinfunction "2_2") (pintype "passive"))
      (node (ref "C200") (pin "2") (pinfunction "2_2") (pintype "passive"))
      (node (ref "C201") (pin "2") (pinfunction "2_2") (pintype "passive"))
      (node (ref "D10") (pin "B10") (pinfunction "VDD_EFVDDQ_B10") (pintype "passive"))
      (node (ref "D10") (pin "C3") (pinfunction "VDD2_C3") (pintype "passive"))
      (node (ref "D10") (pin "E9") (pinfunction "VDD4_E9") (pintype "passive"))
      (node (ref "D10") (pin "F11") (pinfunction "VDD5_F11") (pintype "passive"))
      (node (ref "D10") (pin "H1") (pinfunction "VDD1_H1") (pintype "passive"))
      (node (ref "D10") (pin "J11") (pinfunction "VDD_SRAM_VDD2_J11") (pintype "passive"))
      (node (ref "D10") (pin "L5") (pinfunction "VDD_SRAM_VDD1_L5") (pintype "passive"))
      (node (ref "D10") (pin "L7") (pinfunction "VDD3_L7") (pintype "passive"))
      (node (ref "D12") (pin "10") (pinfunction "Vout_10") (pintype "passive"))
      (node (ref "D12") (pin "11") (pinfunction "Vout_11") (pintype "passive"))
      (node (ref "D12") (pin "12") (pinfunction "Vout_12") (pintype "passive"))
      (node (ref "D12") (pin "13") (pinfunction "Vout_13") (pintype "passive"))
      (node (ref "D12") (pin "14") (pinfunction "Vout_14") (pintype "passive"))
      (node (ref "L10") (pin "1") (pinfunction "1_1") (pintype "passive"))
      (node (ref "L11") (pin "1") (pinfunction "1_1") (pintype "passive"))
      (node (ref "L12") (pin "1") (pinfunction "1_1") (pintype "passive"))
      (node (ref "R82") (pin "2") (pinfunction "2_2") (pintype "passive"))
    )
    (net (code "102") (name "/v1p8d") (class "Default")
      (node (ref "C202") (pin "2") (pinfunction "2_2") (pintype "passive"))
      (node (ref "C203") (pin "2") (pinfunction "2_2") (pintype "passive"))
      (node (ref "C204") (pin "2") (pinfunction "2_2") (pintype "passive"))
      (node (ref "C205") (pin "2") (pinfunction "2_2") (pintype "passive"))
      (node (ref "C206") (pin "2") (pinfunction "2_2") (pintype "passive"))
      (node (ref "C207") (pin "2") (pinfunction "2_2") (pintype "passive"))
      (node (ref "C208") (pin "2") (pinfunction "2_2") (pintype "passive"))
      (node (ref "D10") (pin "B1") (pinfunction "VIO4_B1") (pintype "passive"))
      (node (ref "D10") (pin "E3") (pinfunction "VIO3_E3") (pintype "passive"))
      (node (ref "D10") (pin "F1") (pinfunction "VIO2_F1") (pintype "passive"))
      (node (ref "D10") (pin "H11") (pinfunction "VIO1_2_H11") (pintype "passive"))
      (node (ref "D10") (pin "L9") (pinfunction "VIO1_1_L9") (pintype "passive"))
      (node (ref "D12") (pin "1") (pinfunction "Vin_1") (pintype "passive"))
      (node (ref "D12") (pin "15") (pinfunction "Vin_15") (pintype "passive"))
      (node (ref "D12") (pin "16") (pinfunction "Vin_16") (pintype "passive"))
      (node (ref "D12") (pin "2") (pinfunction "Vin_2") (pintype "passive"))
      (node (ref "D12") (pin "3") (pinfunction "Vin_3") (pintype "passive"))
      (node (ref "D12") (pin "4") (pinfunction "EN_4") (pintype "passive"))
      (node (ref "R77") (pin "2") (pinfunction "2_2") (pintype "passive"))
      (node (ref "R78") (pin "2") (pinfunction "2_2") (pintype "passive"))
      (node (ref "R81") (pin "2") (pinfunction "2_2") (pintype "passive"))
      (node (ref "R84") (pin "2") (pinfunction "2_2") (pintype "passive"))
    )
    (net (code "103") (name "/v3p3d") (class "Default")
      (node (ref "C209") (pin "2") (pinfunction "2_2") (pintype "passive"))
      (node (ref "C210") (pin "2") (pinfunction "2_2") (pintype "passive"))
      (node (ref "C211") (pin "2") (pinfunction "2_2") (pintype "passive"))
      (node (ref "C212") (pin "2") (pinfunction "2_2") (pintype "passive"))
      (node (ref "C213") (pin "2") (pinfunction "2_2") (pintype "passive"))
      (node (ref "C214") (pin "2") (pinfunction "2_2") (pintype "passive"))
      (node (ref "D10") (pin "B6") (pinfunction "CVDDQ_B6") (pintype "passive"))
      (node (ref "D10") (pin "C11") (pinfunction "VIO5_C11") (pintype "passive"))
      (node (ref "D10") (pin "E10") (pinfunction "VBAT_E10") (pintype "passive"))
      (node (ref "D11") (pin "8") (pinfunction "VCC_8") (pintype "power_in"))
      (node (ref "R108") (pin "1") (pinfunction "1_1") (pintype "passive"))
      (node (ref "R62") (pin "1") (pinfunction "1_1") (pintype "passive"))
      (node (ref "R75") (pin "2") (pinfunction "2_2") (pintype "passive"))
      (node (ref "R76") (pin "2") (pinfunction "2_2") (pintype "passive"))
      (node (ref "VG1") (pin "4") (pinfunction "Vcc_4") (pintype "passive"))
    )
    (net (code "104") (name "Net-(D10A-INT_N_CTL15)") (class "Default")
      (node (ref "D10") (pin "L8") (pinfunction "INT_N_CTL15_L8") (pintype "passive"))
      (node (ref "R80") (pin "1") (pinfunction "1_1") (pintype "passive"))
    )
    (net (code "105") (name "Net-(D10A-PMODE0)") (class "Default")
      (node (ref "D10") (pin "G4") (pinfunction "PMODE0_G4") (pintype "passive"))
      (node (ref "R77") (pin "1") (pinfunction "1_1") (pintype "passive"))
    )
    (net (code "106") (name "Net-(D10A-PMODE1)") (class "Default")
      (node (ref "D10") (pin "H4") (pinfunction "PMODE1_H4") (pintype "passive"))
      (node (ref "R78") (pin "1") (pinfunction "1_1") (pintype "passive"))
    )
    (net (code "107") (name "Net-(D10A-PMODE2)") (class "Default")
      (node (ref "D10") (pin "L4") (pinfunction "PMODE2_L4") (pintype "passive"))
      (node (ref "R79") (pin "1") (pinfunction "1_1") (pintype "passive"))
    )
    (net (code "108") (name "Net-(D10A-RESET_N)") (class "Default")
      (node (ref "C187") (pin "2") (pinfunction "2_2") (pintype "passive"))
      (node (ref "D10") (pin "C5") (pinfunction "RESET_N_C5") (pintype "passive"))
      (node (ref "R81") (pin "1") (pinfunction "1_1") (pintype "passive"))
    )
    (net (code "109") (name "Net-(D10D-OTG_ID)") (class "Default")
      (node (ref "D10") (pin "C9") (pinfunction "OTG_ID_C9") (pintype "passive"))
      (node (ref "R60") (pin "1") (pinfunction "1_1") (pintype "passive"))
    )
    (net (code "110") (name "Net-(D10D-R_USB2)") (class "Default")
      (node (ref "D10") (pin "C8") (pinfunction "R_USB2_C8") (pintype "passive"))
      (node (ref "R109") (pin "1") (pinfunction "1_1") (pintype "passive"))
    )
    (net (code "111") (name "Net-(D10D-R_USB3)") (class "Default")
      (node (ref "D10") (pin "B3") (pinfunction "R_USB3_B3") (pintype "passive"))
      (node (ref "R68") (pin "1") (pinfunction "1_1") (pintype "passive"))
    )
    (net (code "112") (name "Net-(D10D-SSTXM)") (class "Default")
      (node (ref "C181") (pin "2") (pinfunction "2_2") (pintype "passive"))
      (node (ref "D10") (pin "A6") (pinfunction "SSTXM_A6") (pintype "passive"))
    )
    (net (code "113") (name "Net-(D10D-SSTXP)") (class "Default")
      (node (ref "C180") (pin "2") (pinfunction "2_2") (pintype "passive"))
      (node (ref "D10") (pin "A5") (pinfunction "SSTXP_A5") (pintype "passive"))
    )
    (net (code "114") (name "Net-(D10D-VBUS)") (class "Default")
      (node (ref "C179") (pin "1") (pinfunction "1_1") (pintype "passive"))
      (node (ref "D10") (pin "E11") (pinfunction "VBUS_E11") (pintype "passive"))
      (node (ref "R57") (pin "1") (pinfunction "1_1") (pintype "passive"))
    )
    (net (code "115") (name "Net-(D10E-FSLC0)") (class "Default")
      (node (ref "D10") (pin "B2") (pinfunction "FSLC0_B2") (pintype "passive"))
      (node (ref "R59") (pin "2") (pinfunction "2_2") (pintype "passive"))
    )
    (net (code "116") (name "Net-(D10E-FSLC1)") (class "Default")
      (node (ref "D10") (pin "B4") (pinfunction "FSLC1_B4") (pintype "passive"))
      (node (ref "R61") (pin "2") (pinfunction "2_2") (pintype "passive"))
    )
    (net (code "117") (name "Net-(D10E-FSLC2)") (class "Default")
      (node (ref "D10") (pin "E6") (pinfunction "FSLC2_E6") (pintype "passive"))
      (node (ref "R62") (pin "2") (pinfunction "2_2") (pintype "passive"))
    )
    (net (code "118") (name "Net-(D10E-XTALIN)") (class "Default")
      (node (ref "C183") (pin "2") (pinfunction "2_2") (pintype "passive"))
      (node (ref "D10") (pin "C6") (pinfunction "XTALIN_C6") (pintype "passive"))
      (node (ref "ZQ1") (pin "2") (pinfunction "2_2") (pintype "passive"))
    )
    (net (code "119") (name "Net-(D10E-XTALOUT)") (class "Default")
      (node (ref "C182") (pin "2") (pinfunction "2_2") (pintype "passive"))
      (node (ref "D10") (pin "C7") (pinfunction "XTALOUT_C7") (pintype "passive"))
      (node (ref "ZQ1") (pin "1") (pinfunction "1_1") (pintype "passive"))
    )
    (net (code "120") (name "Net-(D12-Adj)") (class "Default")
      (node (ref "D12") (pin "9") (pinfunction "Adj_9") (pintype "passive"))
      (node (ref "R82") (pin "1") (pinfunction "1_1") (pintype "passive"))
      (node (ref "R83") (pin "2") (pinfunction "2_2") (pintype "passive"))
    )
    (net (code "121") (name "Net-(D12-PG)") (class "Default")
      (node (ref "D12") (pin "5") (pinfunction "PG_5") (pintype "passive"))
      (node (ref "R84") (pin "1") (pinfunction "1_1") (pintype "passive"))
    )
    (net (code "122") (name "Net-(VG1-EN)") (class "Default")
      (node (ref "R108") (pin "2") (pinfunction "2_2") (pintype "passive"))
      (node (ref "VG1") (pin "1") (pinfunction "EN_1") (pintype "passive"))
    )
    (net (code "123") (name "Net-(X4-VBUS)") (class "Default")
      (node (ref "R57") (pin "2") (pinfunction "2_2") (pintype "passive"))
      (node (ref "X4") (pin "1") (pinfunction "VBUS_1") (pintype "passive"))
    )
    (net (code "124") (name "unconnected-(D10B-GPIO45-PadF2)") (class "Default")
      (node (ref "D10") (pin "F2") (pinfunction "GPIO45_F2") (pintype "passive"))
    )
    (net (code "125") (name "unconnected-(D10C-I2S-CLK-PadD1)") (class "Default")
      (node (ref "D10") (pin "D1") (pinfunction "I2S-CLK_D1") (pintype "passive"))
    )
    (net (code "126") (name "unconnected-(D10C-I2S-MCLK-PadC4)") (class "Default")
      (node (ref "D10") (pin "C4") (pinfunction "I2S-MCLK_C4") (pintype "passive"))
    )
    (net (code "127") (name "unconnected-(D10C-UART-TX_SPI-MISO-PadC2)") (class "Default")
      (node (ref "D10") (pin "C2") (pinfunction "UART-TX_SPI-MISO_C2") (pintype "passive"))
    )
    (net (code "128") (name "unconnected-(D10D-NC-PadA11)") (class "Default")
      (node (ref "D10") (pin "A11") (pinfunction "NC_A11") (pintype "passive"))
    )
    (net (code "129") (name "unconnected-(D10E-CLKIN_32-PadD6)") (class "Default")
      (node (ref "D10") (pin "D6") (pinfunction "CLKIN_32_D6") (pintype "passive"))
    )
    (net (code "130") (name "unconnected-(D10F-I2C-GPIO60_CHARGER-DETECT-PadD11)") (class "Default")
      (node (ref "D10") (pin "D11") (pinfunction "I2C-GPIO60_CHARGER-DETECT_D11") (pintype "passive"))
    )
    (net (code "131") (name "unconnected-(D10F-TCK-PadF6)") (class "Default")
      (node (ref "D10") (pin "F6") (pinfunction "TCK_F6") (pintype "passive"))
    )
    (net (code "132") (name "unconnected-(D10F-TDI-PadE7)") (class "Default")
      (node (ref "D10") (pin "E7") (pinfunction "TDI_E7") (pintype "passive"))
    )
    (net (code "133") (name "unconnected-(D10F-TDO-PadC10)") (class "Default")
      (node (ref "D10") (pin "C10") (pinfunction "TDO_C10") (pintype "passive"))
    )
    (net (code "134") (name "unconnected-(D10F-TMS-PadE8)") (class "Default")
      (node (ref "D10") (pin "E8") (pinfunction "TMS_E8") (pintype "passive"))
    )
    (net (code "135") (name "unconnected-(D10F-TRST_N-PadB11)") (class "Default")
      (node (ref "D10") (pin "B11") (pinfunction "TRST_N_B11") (pintype "passive"))
    )
    (net (code "136") (name "unconnected-(D12-NC-Pad8)") (class "Default")
      (node (ref "D12") (pin "8") (pinfunction "NC_8") (pintype "passive"))
    )
    (net (code "137") (name "unconnected-(D12-SS-Pad7)") (class "Default")
      (node (ref "D12") (pin "7") (pinfunction "SS_7") (pintype "passive"))
    )
    (net (code "138") (name "unconnected-(R63-Pad5)") (class "Default")
      (node (ref "R63") (pin "5") (pinfunction "5_5") (pintype "passive"))
    )
    (net (code "139") (name "unconnected-(R63-Pad6)") (class "Default")
      (node (ref "R63") (pin "6") (pinfunction "6_6") (pintype "passive"))
    )
    (net (code "140") (name "unconnected-(R63-Pad7)") (class "Default")
      (node (ref "R63") (pin "7") (pinfunction "7_7") (pintype "passive"))
    )
    (net (code "141") (name "unconnected-(R63-Pad8)") (class "Default")
      (node (ref "R63") (pin "8") (pinfunction "8_8") (pintype "passive"))
    )
    (net (code "142") (name "unconnected-(R64-Pad5)") (class "Default")
      (node (ref "R64") (pin "5") (pinfunction "5_5") (pintype "passive"))
    )
    (net (code "143") (name "unconnected-(R64-Pad6)") (class "Default")
      (node (ref "R64") (pin "6") (pinfunction "6_6") (pintype "passive"))
    )
    (net (code "144") (name "unconnected-(R64-Pad7)") (class "Default")
      (node (ref "R64") (pin "7") (pinfunction "7_7") (pintype "passive"))
    )
    (net (code "145") (name "unconnected-(R64-Pad8)") (class "Default")
      (node (ref "R64") (pin "8") (pinfunction "8_8") (pintype "passive"))
    )
    (net (code "146") (name "unconnected-(R67-Pad5)") (class "Default")
      (node (ref "R67") (pin "5") (pinfunction "5_5") (pintype "passive"))
    )
    (net (code "147") (name "unconnected-(R67-Pad6)") (class "Default")
      (node (ref "R67") (pin "6") (pinfunction "6_6") (pintype "passive"))
    )
    (net (code "148") (name "unconnected-(R67-Pad7)") (class "Default")
      (node (ref "R67") (pin "7") (pinfunction "7_7") (pintype "passive"))
    )
    (net (code "149") (name "unconnected-(R67-Pad8)") (class "Default")
      (node (ref "R67") (pin "8") (pinfunction "8_8") (pintype "passive"))
    )
    (net (code "150") (name "unconnected-(R69-Pad5)") (class "Default")
      (node (ref "R69") (pin "5") (pinfunction "5_5") (pintype "passive"))
    )
    (net (code "151") (name "unconnected-(R69-Pad6)") (class "Default")
      (node (ref "R69") (pin "6") (pinfunction "6_6") (pintype "passive"))
    )
    (net (code "152") (name "unconnected-(R69-Pad7)") (class "Default")
      (node (ref "R69") (pin "7") (pinfunction "7_7") (pintype "passive"))
    )
    (net (code "153") (name "unconnected-(R69-Pad8)") (class "Default")
      (node (ref "R69") (pin "8") (pinfunction "8_8") (pintype "passive"))
    )
    (net (code "154") (name "unconnected-(R71-Pad5)") (class "Default")
      (node (ref "R71") (pin "5") (pinfunction "5_5") (pintype "passive"))
    )
    (net (code "155") (name "unconnected-(R71-Pad6)") (class "Default")
      (node (ref "R71") (pin "6") (pinfunction "6_6") (pintype "passive"))
    )
    (net (code "156") (name "unconnected-(R71-Pad7)") (class "Default")
      (node (ref "R71") (pin "7") (pinfunction "7_7") (pintype "passive"))
    )
    (net (code "157") (name "unconnected-(R71-Pad8)") (class "Default")
      (node (ref "R71") (pin "8") (pinfunction "8_8") (pintype "passive"))
    )
    (net (code "158") (name "unconnected-(R72-Pad5)") (class "Default")
      (node (ref "R72") (pin "5") (pinfunction "5_5") (pintype "passive"))
    )
    (net (code "159") (name "unconnected-(R72-Pad6)") (class "Default")
      (node (ref "R72") (pin "6") (pinfunction "6_6") (pintype "passive"))
    )
    (net (code "160") (name "unconnected-(R72-Pad7)") (class "Default")
      (node (ref "R72") (pin "7") (pinfunction "7_7") (pintype "passive"))
    )
    (net (code "161") (name "unconnected-(R72-Pad8)") (class "Default")
      (node (ref "R72") (pin "8") (pinfunction "8_8") (pintype "passive"))
    )
    (net (code "162") (name "unconnected-(R73-Pad5)") (class "Default")
      (node (ref "R73") (pin "5") (pinfunction "5_5") (pintype "passive"))
    )
    (net (code "163") (name "unconnected-(R73-Pad6)") (class "Default")
      (node (ref "R73") (pin "6") (pinfunction "6_6") (pintype "passive"))
    )
    (net (code "164") (name "unconnected-(R73-Pad7)") (class "Default")
      (node (ref "R73") (pin "7") (pinfunction "7_7") (pintype "passive"))
    )
    (net (code "165") (name "unconnected-(R73-Pad8)") (class "Default")
      (node (ref "R73") (pin "8") (pinfunction "8_8") (pintype "passive"))
    )
    (net (code "166") (name "unconnected-(R74-Pad3)") (class "Default")
      (node (ref "R74") (pin "3") (pinfunction "3_3") (pintype "passive"))
    )
    (net (code "167") (name "unconnected-(R74-Pad4)") (class "Default")
      (node (ref "R74") (pin "4") (pinfunction "4_4") (pintype "passive"))
    )
    (net (code "168") (name "unconnected-(R74-Pad5)") (class "Default")
      (node (ref "R74") (pin "5") (pinfunction "5_5") (pintype "passive"))
    )
    (net (code "169") (name "unconnected-(R74-Pad6)") (class "Default")
      (node (ref "R74") (pin "6") (pinfunction "6_6") (pintype "passive"))
    )
    (net (code "170") (name "unconnected-(R74-Pad7)") (class "Default")
      (node (ref "R74") (pin "7") (pinfunction "7_7") (pintype "passive"))
    )
    (net (code "171") (name "unconnected-(R74-Pad8)") (class "Default")
      (node (ref "R74") (pin "8") (pinfunction "8_8") (pintype "passive"))
    )
  )
)
